# digital.net
KiCad netlist of a schematic drawn in Altium Designer
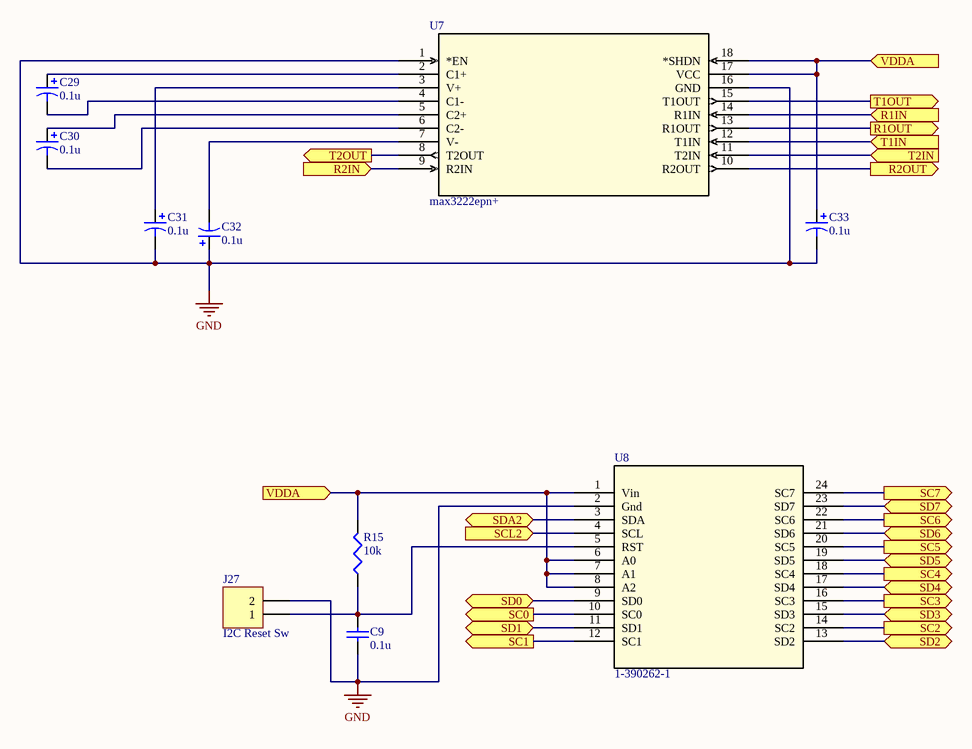
[diagram p0: digital.SchDoc]

(export (version "E")
  (design (tool "Eeschema 10.0.6"))
  (components
    (comp (ref "C9")
      (value "0.1u")
      (footprint "C1206")
      (description "Capacitor (Semiconductor SIM Model)")
      (fields (field (name "PUBLISHER") "Altium Limited"))
      (libsource (lib "Miscellaneous Devices") (part "Cap Semi"))
    )
    (comp (ref "C29")
      (value "0.1u")
      (footprint "C0805")
      (description "Polarized Capacitor (Surface Mount)")
      (fields (field (name "PUBLISHER") "Altium Limited"))
      (libsource (lib "Miscellaneous Devices") (part "Cap Pol3"))
    )
    (comp (ref "C30")
      (value "0.1u")
      (footprint "C0805")
      (description "Polarized Capacitor (Surface Mount)")
      (fields (field (name "PUBLISHER") "Altium Limited"))
      (libsource (lib "Miscellaneous Devices") (part "Cap Pol3"))
    )
    (comp (ref "C31")
      (value "0.1u")
      (footprint "C0805")
      (description "Polarized Capacitor (Surface Mount)")
      (fields (field (name "PUBLISHER") "Altium Limited"))
      (libsource (lib "Miscellaneous Devices") (part "Cap Pol3"))
    )
    (comp (ref "C32")
      (value "0.1u")
      (footprint "C0805")
      (description "Polarized Capacitor (Surface Mount)")
      (fields (field (name "PUBLISHER") "Altium Limited"))
      (libsource (lib "Miscellaneous Devices") (part "Cap Pol3"))
    )
    (comp (ref "C33")
      (value "0.1u")
      (footprint "C0805")
      (description "Polarized Capacitor (Surface Mount)")
      (fields (field (name "PUBLISHER") "Altium Limited"))
      (libsource (lib "Miscellaneous Devices") (part "Cap Pol3"))
    )
    (comp (ref "J27")
      (value "I2C Reset Sw")
      (footprint "HDR1X2")
      (fields (field (name "PUBLISHER") "Altium Limited"))
      (libsource (lib "Miscellaneous Connectors") (part "Header 2"))
    )
    (comp (ref "R15")
      (value "10k")
      (footprint "J1-0603")
      (description "Resistor")
      (fields (field (name "PUBLISHER") "Altium Limited"))
      (libsource (lib "Miscellaneous Devices") (part "Res3"))
    )
    (comp (ref "U7")
      (value "max3222epn+")
      (footprint "21-0043D_18_MXM")
      (description "No Description Available")
      (fields (field (name "COPYRIGHT") "Copyright (C) 2022 Ultra Librarian. All rights reserved."))
      (libsource (lib "max3222epn&plus_") (part "max3222epn+"))
    )
    (comp (ref "U8")
      (value "1-390262-1")
      (footprint "1-390262-1_TYC")
      (description "No Description Available")
      (fields (field (name "COPYRIGHT") "Copyright (C) 2022 Ultra Librarian. All rights reserved."))
      (libsource (lib "1-390262-1") (part "1-390262-1"))
    )
  )
  (nets
    (net (code "1") (name "/R1IN") (class "Default")
      (node (ref "U7") (pin "14") (pinfunction "R1IN_14") (pintype "input"))
    )
    (net (code "2") (name "/R1OUT") (class "Default")
      (node (ref "U7") (pin "13") (pinfunction "R1OUT_13") (pintype "output"))
    )
    (net (code "3") (name "/R2IN") (class "Default")
      (node (ref "U7") (pin "9") (pinfunction "R2IN_9") (pintype "input"))
    )
    (net (code "4") (name "/R2OUT") (class "Default")
      (node (ref "U7") (pin "10") (pinfunction "R2OUT_10") (pintype "output"))
    )
    (net (code "5") (name "/SC0") (class "Default")
      (node (ref "U8") (pin "10") (pinfunction "SC0_10") (pintype "passive"))
    )
    (net (code "6") (name "/SC1") (class "Default")
      (node (ref "U8") (pin "12") (pinfunction "SC1_12") (pintype "passive"))
    )
    (net (code "7") (name "/SC2") (class "Default")
      (node (ref "U8") (pin "14") (pinfunction "SC2_14") (pintype "passive"))
    )
    (net (code "8") (name "/SC3") (class "Default")
      (node (ref "U8") (pin "16") (pinfunction "SC3_16") (pintype "passive"))
    )
    (net (code "9") (name "/SC4") (class "Default")
      (node (ref "U8") (pin "18") (pinfunction "SC4_18") (pintype "passive"))
    )
    (net (code "10") (name "/SC5") (class "Default")
      (node (ref "U8") (pin "20") (pinfunction "SC5_20") (pintype "passive"))
    )
    (net (code "11") (name "/SC6") (class "Default")
      (node (ref "U8") (pin "22") (pinfunction "SC6_22") (pintype "passive"))
    )
    (net (code "12") (name "/SC7") (class "Default")
      (node (ref "U8") (pin "24") (pinfunction "SC7_24") (pintype "passive"))
    )
    (net (code "13") (name "/SCL2") (class "Default")
      (node (ref "U8") (pin "4") (pinfunction "SCL_4") (pintype "passive"))
    )
    (net (code "14") (name "/SD0") (class "Default")
      (node (ref "U8") (pin "9") (pinfunction "SD0_9") (pintype "passive"))
    )
    (net (code "15") (name "/SD1") (class "Default")
      (node (ref "U8") (pin "11") (pinfunction "SD1_11") (pintype "passive"))
    )
    (net (code "16") (name "/SD2") (class "Default")
      (node (ref "U8") (pin "13") (pinfunction "SD2_13") (pintype "passive"))
    )
    (net (code "17") (name "/SD3") (class "Default")
      (node (ref "U8") (pin "15") (pinfunction "SD3_15") (pintype "passive"))
    )
    (net (code "18") (name "/SD4") (class "Default")
      (node (ref "U8") (pin "17") (pinfunction "SD4_17") (pintype "passive"))
    )
    (net (code "19") (name "/SD5") (class "Default")
      (node (ref "U8") (pin "19") (pinfunction "SD5_19") (pintype "passive"))
    )
    (net (code "20") (name "/SD6") (class "Default")
      (node (ref "U8") (pin "21") (pinfunction "SD6_21") (pintype "passive"))
    )
    (net (code "21") (name "/SD7") (class "Default")
      (node (ref "U8") (pin "23") (pinfunction "SD7_23") (pintype "passive"))
    )
    (net (code "22") (name "/SDA2") (class "Default")
      (node (ref "U8") (pin "3") (pinfunction "SDA_3") (pintype "passive"))
    )
    (net (code "23") (name "/T1IN") (class "Default")
      (node (ref "U7") (pin "12") (pinfunction "T1IN_12") (pintype "input"))
    )
    (net (code "24") (name "/T1OUT") (class "Default")
      (node (ref "U7") (pin "15") (pinfunction "T1OUT_15") (pintype "output"))
    )
    (net (code "25") (name "/T2IN") (class "Default")
      (node (ref "U7") (pin "11") (pinfunction "T2IN_11") (pintype "input"))
    )
    (net (code "26") (name "/T2OUT") (class "Default")
      (node (ref "U7") (pin "8") (pinfunction "T2OUT_8") (pintype "output"))
    )
    (net (code "27") (name "/VDDA") (class "Default")
      (node (ref "C33") (pin "1") (pinfunction "1_1") (pintype "passive"))
      (node (ref "R15") (pin "2") (pinfunction "2_2") (pintype "passive"))
      (node (ref "U7") (pin "17") (pinfunction "VCC_17") (pintype "power_in"))
      (node (ref "U7") (pin "18") (pinfunction "*SHDN_18") (pintype "input"))
      (node (ref "U8") (pin "1") (pinfunction "Vin_1") (pintype "passive"))
      (node (ref "U8") (pin "6") (pinfunction "A0_6") (pintype "passive"))
      (node (ref "U8") (pin "7") (pinfunction "A1_7") (pintype "passive"))
      (node (ref "U8") (pin "8") (pinfunction "A2_8") (pintype "passive"))
    )
    (net (code "28") (name "GND") (class "Default")
      (node (ref "C31") (pin "2") (pinfunction "2_2") (pintype "passive"))
      (node (ref "C32") (pin "1") (pinfunction "1_1") (pintype "passive"))
      (node (ref "C33") (pin "2") (pinfunction "2_2") (pintype "passive"))
      (node (ref "C9") (pin "1") (pinfunction "1_1") (pintype "passive"))
      (node (ref "J27") (pin "2") (pinfunction "2_2") (pintype "passive"))
      (node (ref "U7") (pin "1") (pinfunction "*EN_1") (pintype "input"))
      (node (ref "U7") (pin "16") (pinfunction "GND_16") (pintype "power_in"))
      (node (ref "U8") (pin "2") (pinfunction "Gnd_2") (pintype "passive"))
    )
    (net (code "29") (name "Net-(U7-C1+)") (class "Default")
      (node (ref "C29") (pin "1") (pinfunction "1_1") (pintype "passive"))
      (node (ref "U7") (pin "2") (pinfunction "C1+_2") (pintype "passive"))
    )
    (net (code "30") (name "Net-(U7-C1-)") (class "Default")
      (node (ref "C29") (pin "2") (pinfunction "2_2") (pintype "passive"))
      (node (ref "U7") (pin "4") (pinfunction "C1-_4") (pintype "passive"))
    )
    (net (code "31") (name "Net-(U7-C2+)") (class "Default")
      (node (ref "C30") (pin "1") (pinfunction "1_1") (pintype "passive"))
      (node (ref "U7") (pin "5") (pinfunction "C2+_5") (pintype "passive"))
    )
    (net (code "32") (name "Net-(U7-C2-)") (class "Default")
      (node (ref "C30") (pin "2") (pinfunction "2_2") (pintype "passive"))
      (node (ref "U7") (pin "6") (pinfunction "C2-_6") (pintype "passive"))
    )
    (net (code "33") (name "Net-(U7-V+)") (class "Default")
      (node (ref "C31") (pin "1") (pinfunction "1_1") (pintype "passive"))
      (node (ref "U7") (pin "3") (pinfunction "V+_3") (pintype "power_in"))
    )
    (net (code "34") (name "Net-(U7-V-)") (class "Default")
      (node (ref "C32") (pin "2") (pinfunction "2_2") (pintype "passive"))
      (node (ref "U7") (pin "7") (pinfunction "V-_7") (pintype "power_in"))
    )
    (net (code "35") (name "Net-(U8-RST)") (class "Default")
      (node (ref "C9") (pin "2") (pinfunction "2_2") (pintype "passive"))
      (node (ref "J27") (pin "1") (pinfunction "1_1") (pintype "passive"))
      (node (ref "R15") (pin "1") (pinfunction "1_1") (pintype "passive"))
      (node (ref "U8") (pin "5") (pinfunction "RST_5") (pintype "passive"))
    )
  )
)
